# BUFFER.net
KiCad netlist of a schematic drawn in EAGLE
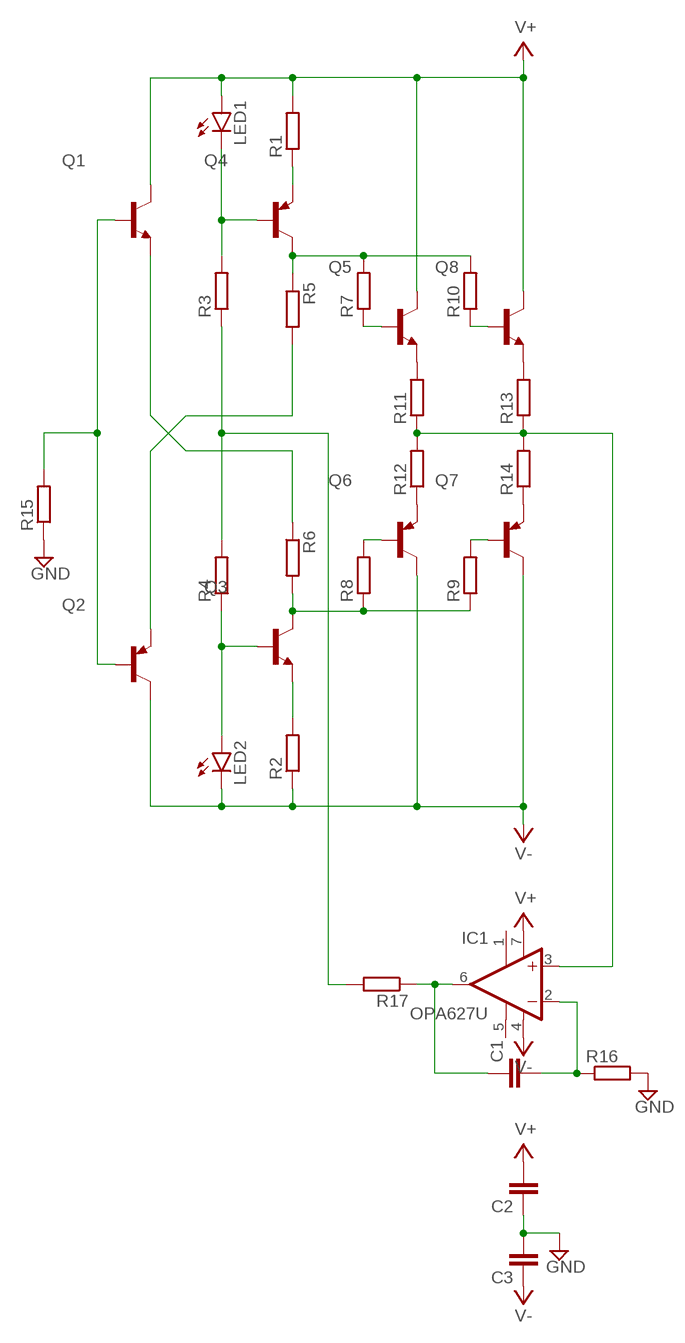
[diagram p0: schematic, sheet 1]

(export (version "E")
  (design (tool "Eeschema 10.0.6"))
  (components
    (comp (ref "C1")
      (value "C-EUC0805")
      (footprint "eagle-import:C0805")
      (libsource (lib "eagle-import") (part "C-EUC0805"))
    )
    (comp (ref "C2")
      (value "C-EUC0805")
      (footprint "eagle-import:C0805")
      (libsource (lib "eagle-import") (part "C-EUC0805"))
    )
    (comp (ref "C3")
      (value "C-EUC0805")
      (footprint "eagle-import:C0805")
      (libsource (lib "eagle-import") (part "C-EUC0805"))
    )
    (comp (ref "IC1")
      (value "OPA627U")
      (footprint "eagle-import:SO08")
      (fields (field (name "MF") "TEXAS INSTRUMENTS") (field (name "MPN") "OPA627AU"))
      (libsource (lib "eagle-import") (part "OPA627U"))
    )
    (comp (ref "LED1")
      (value "LEDCHIPLED_1206")
      (footprint "eagle-import:CHIPLED_1206")
      (libsource (lib "eagle-import") (part "LEDCHIPLED_1206"))
    )
    (comp (ref "LED2")
      (value "LEDCHIPLED_1206")
      (footprint "eagle-import:CHIPLED_1206")
      (libsource (lib "eagle-import") (part "LEDCHIPLED_1206"))
    )
    (comp (ref "Q1")
      (value "TRANSISTOR_BC846-NPN-SOT23-BEC")
      (footprint "eagle-import:TRANSISTOR_SOT23-BEC")
      (libsource (lib "eagle-import") (part "TRANSISTOR_-NPN-SOT23-BECBC846"))
    )
    (comp (ref "Q2")
      (value "TRANSISTOR_BC856B-PNP-SOT23-BEC")
      (footprint "eagle-import:TRANSISTOR_SOT23-BEC")
      (libsource (lib "eagle-import") (part "TRANSISTOR_-PNP-SOT23-BECBC856B"))
    )
    (comp (ref "Q3")
      (value "TRANSISTOR_BC846-NPN-SOT23-BEC")
      (footprint "eagle-import:TRANSISTOR_SOT23-BEC")
      (libsource (lib "eagle-import") (part "TRANSISTOR_-NPN-SOT23-BECBC846"))
    )
    (comp (ref "Q4")
      (value "TRANSISTOR_BC856B-PNP-SOT23-BEC")
      (footprint "eagle-import:TRANSISTOR_SOT23-BEC")
      (libsource (lib "eagle-import") (part "TRANSISTOR_-PNP-SOT23-BECBC856B"))
    )
    (comp (ref "Q5")
      (value "TRANSISTOR_BC846-NPN-SOT23-BEC")
      (footprint "eagle-import:TRANSISTOR_SOT23-BEC")
      (libsource (lib "eagle-import") (part "TRANSISTOR_-NPN-SOT23-BECBC846"))
    )
    (comp (ref "Q6")
      (value "TRANSISTOR_BC856B-PNP-SOT23-BEC")
      (footprint "eagle-import:TRANSISTOR_SOT23-BEC")
      (libsource (lib "eagle-import") (part "TRANSISTOR_-PNP-SOT23-BECBC856B"))
    )
    (comp (ref "Q7")
      (value "TRANSISTOR_BC856B-PNP-SOT23-BEC")
      (footprint "eagle-import:TRANSISTOR_SOT23-BEC")
      (libsource (lib "eagle-import") (part "TRANSISTOR_-PNP-SOT23-BECBC856B"))
    )
    (comp (ref "Q8")
      (value "TRANSISTOR_BC846-NPN-SOT23-BEC")
      (footprint "eagle-import:TRANSISTOR_SOT23-BEC")
      (libsource (lib "eagle-import") (part "TRANSISTOR_-NPN-SOT23-BECBC846"))
    )
    (comp (ref "R1")
      (value "R-EU_MELF0204R")
      (footprint "eagle-import:MINI_MELF-0204R")
      (libsource (lib "eagle-import") (part "R-EU_MELF0204R"))
    )
    (comp (ref "R2")
      (value "R-EU_MELF0204R")
      (footprint "eagle-import:MINI_MELF-0204R")
      (libsource (lib "eagle-import") (part "R-EU_MELF0204R"))
    )
    (comp (ref "R3")
      (value "R-EU_MELF0204R")
      (footprint "eagle-import:MINI_MELF-0204R")
      (libsource (lib "eagle-import") (part "R-EU_MELF0204R"))
    )
    (comp (ref "R4")
      (value "R-EU_MELF0204R")
      (footprint "eagle-import:MINI_MELF-0204R")
      (libsource (lib "eagle-import") (part "R-EU_MELF0204R"))
    )
    (comp (ref "R5")
      (value "R-EU_MELF0204R")
      (footprint "eagle-import:MINI_MELF-0204R")
      (libsource (lib "eagle-import") (part "R-EU_MELF0204R"))
    )
    (comp (ref "R6")
      (value "R-EU_MELF0204R")
      (footprint "eagle-import:MINI_MELF-0204R")
      (libsource (lib "eagle-import") (part "R-EU_MELF0204R"))
    )
    (comp (ref "R7")
      (value "R-EU_MELF0204R")
      (footprint "eagle-import:MINI_MELF-0204R")
      (libsource (lib "eagle-import") (part "R-EU_MELF0204R"))
    )
    (comp (ref "R8")
      (value "R-EU_MELF0204R")
      (footprint "eagle-import:MINI_MELF-0204R")
      (libsource (lib "eagle-import") (part "R-EU_MELF0204R"))
    )
    (comp (ref "R9")
      (value "R-EU_MELF0204R")
      (footprint "eagle-import:MINI_MELF-0204R")
      (libsource (lib "eagle-import") (part "R-EU_MELF0204R"))
    )
    (comp (ref "R10")
      (value "R-EU_MELF0204R")
      (footprint "eagle-import:MINI_MELF-0204R")
      (libsource (lib "eagle-import") (part "R-EU_MELF0204R"))
    )
    (comp (ref "R11")
      (value "R-EU_MELF0204R")
      (footprint "eagle-import:MINI_MELF-0204R")
      (libsource (lib "eagle-import") (part "R-EU_MELF0204R"))
    )
    (comp (ref "R12")
      (value "R-EU_MELF0204R")
      (footprint "eagle-import:MINI_MELF-0204R")
      (libsource (lib "eagle-import") (part "R-EU_MELF0204R"))
    )
    (comp (ref "R13")
      (value "R-EU_MELF0204R")
      (footprint "eagle-import:MINI_MELF-0204R")
      (libsource (lib "eagle-import") (part "R-EU_MELF0204R"))
    )
    (comp (ref "R14")
      (value "R-EU_MELF0204R")
      (footprint "eagle-import:MINI_MELF-0204R")
      (libsource (lib "eagle-import") (part "R-EU_MELF0204R"))
    )
    (comp (ref "R15")
      (value "R-EU_MELF0204R")
      (footprint "eagle-import:MINI_MELF-0204R")
      (libsource (lib "eagle-import") (part "R-EU_MELF0204R"))
    )
    (comp (ref "R16")
      (value "R-EU_MELF0204R")
      (footprint "eagle-import:MINI_MELF-0204R")
      (libsource (lib "eagle-import") (part "R-EU_MELF0204R"))
    )
    (comp (ref "R17")
      (value "R-EU_MELF0204R")
      (footprint "eagle-import:MINI_MELF-0204R")
      (libsource (lib "eagle-import") (part "R-EU_MELF0204R"))
    )
  )
  (nets
    (net (code "1") (name "GND") (class "Default")
      (node (ref "C2") (pin "1") (pinfunction "1_1") (pintype "passive"))
      (node (ref "C3") (pin "2") (pinfunction "2_2") (pintype "passive"))
      (node (ref "R15") (pin "1") (pinfunction "1_1") (pintype "passive"))
      (node (ref "R16") (pin "2") (pinfunction "2_2") (pintype "passive"))
    )
    (net (code "2") (name "Net-(IC1-+IN)") (class "Default")
      (node (ref "IC1") (pin "3") (pinfunction "+IN_3") (pintype "input"))
      (node (ref "R11") (pin "1") (pinfunction "1_1") (pintype "passive"))
      (node (ref "R12") (pin "2") (pinfunction "2_2") (pintype "passive"))
      (node (ref "R13") (pin "1") (pinfunction "1_1") (pintype "passive"))
      (node (ref "R14") (pin "2") (pinfunction "2_2") (pintype "passive"))
    )
    (net (code "3") (name "Net-(IC1--IN)") (class "Default")
      (node (ref "C1") (pin "2") (pinfunction "2_2") (pintype "passive"))
      (node (ref "IC1") (pin "2") (pinfunction "-IN_2") (pintype "input"))
      (node (ref "R16") (pin "1") (pinfunction "1_1") (pintype "passive"))
    )
    (net (code "4") (name "Net-(IC1-OUT)") (class "Default")
      (node (ref "C1") (pin "1") (pinfunction "1_1") (pintype "passive"))
      (node (ref "IC1") (pin "6") (pinfunction "OUT_6") (pintype "output"))
      (node (ref "R17") (pin "1") (pinfunction "1_1") (pintype "passive"))
    )
    (net (code "5") (name "Net-(LED1-PadC)") (class "Default")
      (node (ref "LED1") (pin "C") (pinfunction "C_C") (pintype "passive"))
      (node (ref "Q4") (pin "B") (pinfunction "B_B") (pintype "passive"))
      (node (ref "R3") (pin "2") (pinfunction "2_2") (pintype "passive"))
    )
    (net (code "6") (name "Net-(LED2-PadA)") (class "Default")
      (node (ref "LED2") (pin "A") (pinfunction "A_A") (pintype "passive"))
      (node (ref "Q3") (pin "B") (pinfunction "B_B") (pintype "passive"))
      (node (ref "R4") (pin "1") (pinfunction "1_1") (pintype "passive"))
    )
    (net (code "7") (name "Net-(Q1-PadB)") (class "Default")
      (node (ref "Q1") (pin "B") (pinfunction "B_B") (pintype "passive"))
      (node (ref "Q2") (pin "B") (pinfunction "B_B") (pintype "passive"))
      (node (ref "R15") (pin "2") (pinfunction "2_2") (pintype "passive"))
    )
    (net (code "8") (name "Net-(Q1-PadE)") (class "Default")
      (node (ref "Q1") (pin "E") (pinfunction "E_E") (pintype "passive"))
      (node (ref "R6") (pin "1") (pinfunction "1_1") (pintype "passive"))
    )
    (net (code "9") (name "Net-(Q2-PadE)") (class "Default")
      (node (ref "Q2") (pin "E") (pinfunction "E_E") (pintype "passive"))
      (node (ref "R5") (pin "2") (pinfunction "2_2") (pintype "passive"))
    )
    (net (code "10") (name "Net-(Q3-PadC)") (class "Default")
      (node (ref "Q3") (pin "C") (pinfunction "C_C") (pintype "passive"))
      (node (ref "R6") (pin "2") (pinfunction "2_2") (pintype "passive"))
      (node (ref "R8") (pin "1") (pinfunction "1_1") (pintype "passive"))
      (node (ref "R9") (pin "1") (pinfunction "1_1") (pintype "passive"))
    )
    (net (code "11") (name "Net-(Q3-PadE)") (class "Default")
      (node (ref "Q3") (pin "E") (pinfunction "E_E") (pintype "passive"))
      (node (ref "R2") (pin "2") (pinfunction "2_2") (pintype "passive"))
    )
    (net (code "12") (name "Net-(Q4-PadC)") (class "Default")
      (node (ref "Q4") (pin "C") (pinfunction "C_C") (pintype "passive"))
      (node (ref "R10") (pin "2") (pinfunction "2_2") (pintype "passive"))
      (node (ref "R5") (pin "1") (pinfunction "1_1") (pintype "passive"))
      (node (ref "R7") (pin "2") (pinfunction "2_2") (pintype "passive"))
    )
    (net (code "13") (name "Net-(Q4-PadE)") (class "Default")
      (node (ref "Q4") (pin "E") (pinfunction "E_E") (pintype "passive"))
      (node (ref "R1") (pin "1") (pinfunction "1_1") (pintype "passive"))
    )
    (net (code "14") (name "Net-(Q5-PadB)") (class "Default")
      (node (ref "Q5") (pin "B") (pinfunction "B_B") (pintype "passive"))
      (node (ref "R7") (pin "1") (pinfunction "1_1") (pintype "passive"))
    )
    (net (code "15") (name "Net-(Q5-PadE)") (class "Default")
      (node (ref "Q5") (pin "E") (pinfunction "E_E") (pintype "passive"))
      (node (ref "R11") (pin "2") (pinfunction "2_2") (pintype "passive"))
    )
    (net (code "16") (name "Net-(Q6-PadB)") (class "Default")
      (node (ref "Q6") (pin "B") (pinfunction "B_B") (pintype "passive"))
      (node (ref "R8") (pin "2") (pinfunction "2_2") (pintype "passive"))
    )
    (net (code "17") (name "Net-(Q6-PadE)") (class "Default")
      (node (ref "Q6") (pin "E") (pinfunction "E_E") (pintype "passive"))
      (node (ref "R12") (pin "1") (pinfunction "1_1") (pintype "passive"))
    )
    (net (code "18") (name "Net-(Q7-PadB)") (class "Default")
      (node (ref "Q7") (pin "B") (pinfunction "B_B") (pintype "passive"))
      (node (ref "R9") (pin "2") (pinfunction "2_2") (pintype "passive"))
    )
    (net (code "19") (name "Net-(Q7-PadE)") (class "Default")
      (node (ref "Q7") (pin "E") (pinfunction "E_E") (pintype "passive"))
      (node (ref "R14") (pin "1") (pinfunction "1_1") (pintype "passive"))
    )
    (net (code "20") (name "Net-(Q8-PadB)") (class "Default")
      (node (ref "Q8") (pin "B") (pinfunction "B_B") (pintype "passive"))
      (node (ref "R10") (pin "1") (pinfunction "1_1") (pintype "passive"))
    )
    (net (code "21") (name "Net-(Q8-PadE)") (class "Default")
      (node (ref "Q8") (pin "E") (pinfunction "E_E") (pintype "passive"))
      (node (ref "R13") (pin "2") (pinfunction "2_2") (pintype "passive"))
    )
    (net (code "22") (name "Net-(R17-Pad2)") (class "Default")
      (node (ref "R17") (pin "2") (pinfunction "2_2") (pintype "passive"))
      (node (ref "R3") (pin "1") (pinfunction "1_1") (pintype "passive"))
      (node (ref "R4") (pin "2") (pinfunction "2_2") (pintype "passive"))
    )
    (net (code "23") (name "V+") (class "Default")
      (node (ref "C2") (pin "2") (pinfunction "2_2") (pintype "passive"))
      (node (ref "IC1") (pin "7") (pinfunction "V+_7") (pintype "power_in"))
      (node (ref "LED1") (pin "A") (pinfunction "A_A") (pintype "passive"))
      (node (ref "Q1") (pin "C") (pinfunction "C_C") (pintype "passive"))
      (node (ref "Q5") (pin "C") (pinfunction "C_C") (pintype "passive"))
      (node (ref "Q8") (pin "C") (pinfunction "C_C") (pintype "passive"))
      (node (ref "R1") (pin "2") (pinfunction "2_2") (pintype "passive"))
    )
    (net (code "24") (name "V-") (class "Default")
      (node (ref "C3") (pin "1") (pinfunction "1_1") (pintype "passive"))
      (node (ref "IC1") (pin "4") (pinfunction "V-_4") (pintype "power_in"))
      (node (ref "LED2") (pin "C") (pinfunction "C_C") (pintype "passive"))
      (node (ref "Q2") (pin "C") (pinfunction "C_C") (pintype "passive"))
      (node (ref "Q6") (pin "C") (pinfunction "C_C") (pintype "passive"))
      (node (ref "Q7") (pin "C") (pinfunction "C_C") (pintype "passive"))
      (node (ref "R2") (pin "1") (pinfunction "1_1") (pintype "passive"))
    )
    (net (code "25") (name "unconnected-(IC1-TRIM1-Pad1)") (class "Default")
      (node (ref "IC1") (pin "1") (pinfunction "TRIM1_1") (pintype "passive"))
    )
    (net (code "26") (name "unconnected-(IC1-TRIM2-Pad5)") (class "Default")
      (node (ref "IC1") (pin "5") (pinfunction "TRIM2_5") (pintype "passive"))
    )
  )
)
